# Black_PSI_Controller.net
KiCad netlist of a schematic drawn in EAGLE
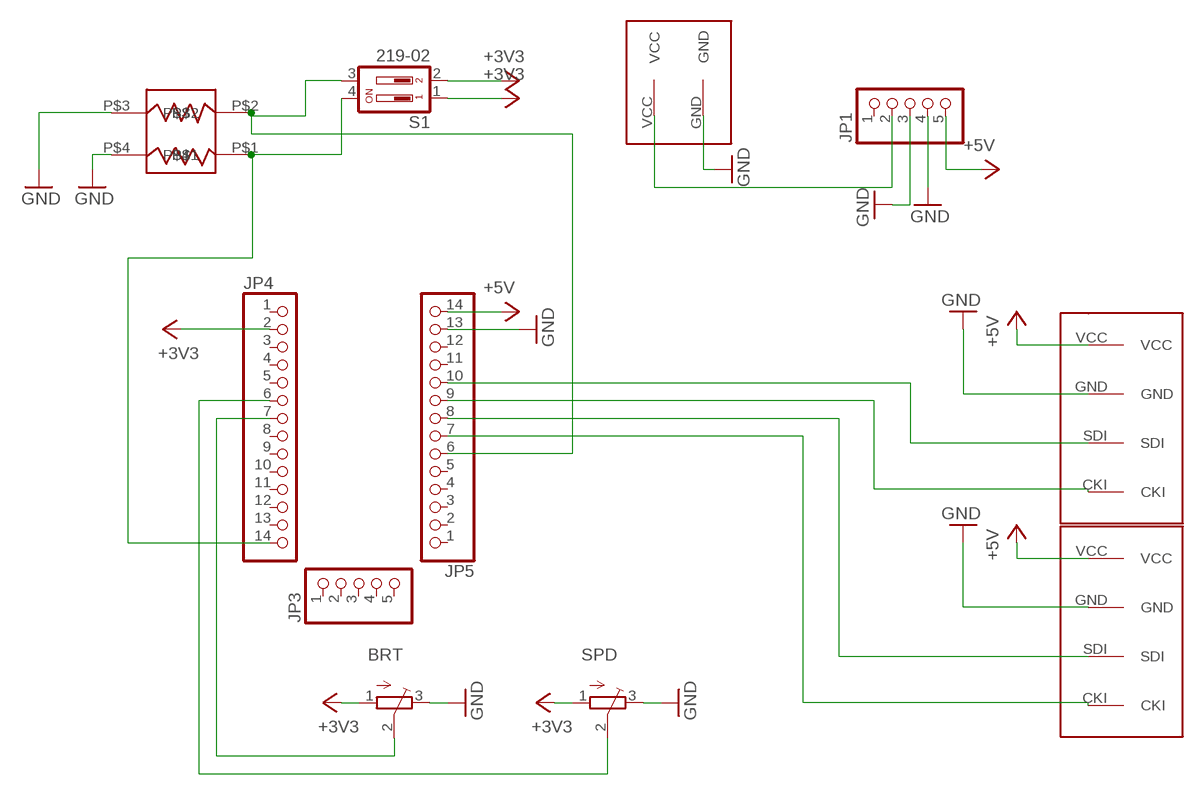
[diagram p0: schematic, sheet 1]

(export (version "E")
  (design (tool "Eeschema 10.0.6"))
  (components
    (comp (ref "BRT")
      (value "TRIMPOTTC33X")
      (footprint "eagle-import:TC33X")
      (libsource (lib "eagle-import") (part "TRIMPOTTC33X"))
    )
    (comp (ref "JP1")
      (value "PINHD-1X5")
      (footprint "eagle-import:1X05")
      (libsource (lib "eagle-import") (part "PINHD-1X5"))
    )
    (comp (ref "JP3")
      (value "PINHD-1X5")
      (footprint "eagle-import:1X05")
      (libsource (lib "eagle-import") (part "PINHD-1X5"))
    )
    (comp (ref "JP4")
      (value "PINHD-1X14")
      (footprint "eagle-import:1X14")
      (libsource (lib "eagle-import") (part "PINHD-1X14"))
    )
    (comp (ref "JP5")
      (value "PINHD-1X14")
      (footprint "eagle-import:1X14")
      (libsource (lib "eagle-import") (part "PINHD-1X14"))
    )
    (comp (ref "S1")
      (value "219-02")
      (footprint "eagle-import:CTS-219-02")
      (libsource (lib "eagle-import") (part "219-02"))
    )
    (comp (ref "SPD")
      (value "TRIMPOTTC33X")
      (footprint "eagle-import:TC33X")
      (libsource (lib "eagle-import") (part "TRIMPOTTC33X"))
    )
    (comp (ref "U$1")
      (value "0393570002WIRE-TO-BOARD")
      (footprint "eagle-import:0393570002WIRE-TO-BOARD")
      (libsource (lib "eagle-import") (part "0393570002WIRE-TO-BOARD"))
    )
    (comp (ref "U$2")
      (value "0393570004WIRE-TO-BOARD")
      (footprint "eagle-import:0393570004WIRE-TO-BOARD")
      (libsource (lib "eagle-import") (part "0393570004WIRE-TO-BOARD"))
    )
    (comp (ref "U$3")
      (value "0393570004WIRE-TO-BOARD")
      (footprint "eagle-import:0393570004WIRE-TO-BOARD")
      (libsource (lib "eagle-import") (part "0393570004WIRE-TO-BOARD"))
    )
    (comp (ref "U$4")
      (value "ACASN1002S1002P1AT")
      (footprint "eagle-import:ACASN1002S1002P1AT")
      (libsource (lib "eagle-import") (part "ACASN1002S1002P1AT"))
    )
  )
  (nets
    (net (code "1") (name "+3V3") (class "Default")
      (node (ref "BRT") (pin "1") (pinfunction "A_1") (pintype "passive"))
      (node (ref "JP4") (pin "2") (pinfunction "2_2") (pintype "passive"))
      (node (ref "S1") (pin "1") (pinfunction "1_1") (pintype "passive"))
      (node (ref "S1") (pin "2") (pinfunction "2_2") (pintype "passive"))
      (node (ref "SPD") (pin "1") (pinfunction "A_1") (pintype "passive"))
    )
    (net (code "2") (name "+5V") (class "Default")
      (node (ref "JP1") (pin "5") (pinfunction "5_5") (pintype "passive"))
      (node (ref "JP5") (pin "14") (pinfunction "14_14") (pintype "passive"))
      (node (ref "U$2") (pin "VCC") (pinfunction "VCC_VCC") (pintype "bidirectional"))
      (node (ref "U$3") (pin "VCC") (pinfunction "VCC_VCC") (pintype "bidirectional"))
    )
    (net (code "3") (name "GND") (class "Default")
      (node (ref "BRT") (pin "3") (pinfunction "E_3") (pintype "passive"))
      (node (ref "JP1") (pin "3") (pinfunction "3_3") (pintype "passive"))
      (node (ref "JP1") (pin "4") (pinfunction "4_4") (pintype "passive"))
      (node (ref "JP5") (pin "13") (pinfunction "13_13") (pintype "passive"))
      (node (ref "SPD") (pin "3") (pinfunction "E_3") (pintype "passive"))
      (node (ref "U$1") (pin "GND") (pinfunction "GND_GND") (pintype "bidirectional"))
      (node (ref "U$2") (pin "GND") (pinfunction "GND_GND") (pintype "bidirectional"))
      (node (ref "U$3") (pin "GND") (pinfunction "GND_GND") (pintype "bidirectional"))
      (node (ref "U$4") (pin "P$3") (pinfunction "P$3_P$3") (pintype "bidirectional"))
      (node (ref "U$4") (pin "P$4") (pinfunction "P$4_P$4") (pintype "bidirectional"))
    )
    (net (code "4") (name "Net-(BRT-S)") (class "Default")
      (node (ref "BRT") (pin "2") (pinfunction "S_2") (pintype "passive"))
      (node (ref "JP4") (pin "7") (pinfunction "7_7") (pintype "passive"))
    )
    (net (code "5") (name "Net-(JP1-Pad2)") (class "Default")
      (node (ref "JP1") (pin "2") (pinfunction "2_2") (pintype "passive"))
      (node (ref "U$1") (pin "VCC") (pinfunction "VCC_VCC") (pintype "bidirectional"))
    )
    (net (code "6") (name "Net-(JP4-Pad14)") (class "Default")
      (node (ref "JP4") (pin "14") (pinfunction "14_14") (pintype "passive"))
      (node (ref "S1") (pin "4") (pinfunction "4_4") (pintype "passive"))
      (node (ref "U$4") (pin "P$1") (pinfunction "P$1_P$1") (pintype "bidirectional"))
    )
    (net (code "7") (name "Net-(JP5-Pad6)") (class "Default")
      (node (ref "JP5") (pin "6") (pinfunction "6_6") (pintype "passive"))
      (node (ref "S1") (pin "3") (pinfunction "3_3") (pintype "passive"))
      (node (ref "U$4") (pin "P$2") (pinfunction "P$2_P$2") (pintype "bidirectional"))
    )
    (net (code "8") (name "Net-(JP5-Pad7)") (class "Default")
      (node (ref "JP5") (pin "7") (pinfunction "7_7") (pintype "passive"))
      (node (ref "U$3") (pin "CKI") (pinfunction "CKI_CKI") (pintype "bidirectional"))
    )
    (net (code "9") (name "Net-(JP5-Pad8)") (class "Default")
      (node (ref "JP5") (pin "8") (pinfunction "8_8") (pintype "passive"))
      (node (ref "U$3") (pin "SDI") (pinfunction "SDI_SDI") (pintype "bidirectional"))
    )
    (net (code "10") (name "Net-(JP5-Pad9)") (class "Default")
      (node (ref "JP5") (pin "9") (pinfunction "9_9") (pintype "passive"))
      (node (ref "U$2") (pin "CKI") (pinfunction "CKI_CKI") (pintype "bidirectional"))
    )
    (net (code "11") (name "Net-(JP5-Pad10)") (class "Default")
      (node (ref "JP5") (pin "10") (pinfunction "10_10") (pintype "passive"))
      (node (ref "U$2") (pin "SDI") (pinfunction "SDI_SDI") (pintype "bidirectional"))
    )
    (net (code "12") (name "Net-(SPD-S)") (class "Default")
      (node (ref "JP4") (pin "6") (pinfunction "6_6") (pintype "passive"))
      (node (ref "SPD") (pin "2") (pinfunction "S_2") (pintype "passive"))
    )
    (net (code "13") (name "unconnected-(JP1-Pad1)") (class "Default")
      (node (ref "JP1") (pin "1") (pinfunction "1_1") (pintype "passive"))
    )
    (net (code "14") (name "unconnected-(JP3-Pad1)") (class "Default")
      (node (ref "JP3") (pin "1") (pinfunction "1_1") (pintype "passive"))
    )
    (net (code "15") (name "unconnected-(JP3-Pad2)") (class "Default")
      (node (ref "JP3") (pin "2") (pinfunction "2_2") (pintype "passive"))
    )
    (net (code "16") (name "unconnected-(JP3-Pad3)") (class "Default")
      (node (ref "JP3") (pin "3") (pinfunction "3_3") (pintype "passive"))
    )
    (net (code "17") (name "unconnected-(JP3-Pad4)") (class "Default")
      (node (ref "JP3") (pin "4") (pinfunction "4_4") (pintype "passive"))
    )
    (net (code "18") (name "unconnected-(JP3-Pad5)") (class "Default")
      (node (ref "JP3") (pin "5") (pinfunction "5_5") (pintype "passive"))
    )
    (net (code "19") (name "unconnected-(JP4-Pad1)") (class "Default")
      (node (ref "JP4") (pin "1") (pinfunction "1_1") (pintype "passive"))
    )
    (net (code "20") (name "unconnected-(JP4-Pad3)") (class "Default")
      (node (ref "JP4") (pin "3") (pinfunction "3_3") (pintype "passive"))
    )
    (net (code "21") (name "unconnected-(JP4-Pad4)") (class "Default")
      (node (ref "JP4") (pin "4") (pinfunction "4_4") (pintype "passive"))
    )
    (net (code "22") (name "unconnected-(JP4-Pad5)") (class "Default")
      (node (ref "JP4") (pin "5") (pinfunction "5_5") (pintype "passive"))
    )
    (net (code "23") (name "unconnected-(JP4-Pad8)") (class "Default")
      (node (ref "JP4") (pin "8") (pinfunction "8_8") (pintype "passive"))
    )
    (net (code "24") (name "unconnected-(JP4-Pad9)") (class "Default")
      (node (ref "JP4") (pin "9") (pinfunction "9_9") (pintype "passive"))
    )
    (net (code "25") (name "unconnected-(JP4-Pad10)") (class "Default")
      (node (ref "JP4") (pin "10") (pinfunction "10_10") (pintype "passive"))
    )
    (net (code "26") (name "unconnected-(JP4-Pad11)") (class "Default")
      (node (ref "JP4") (pin "11") (pinfunction "11_11") (pintype "passive"))
    )
    (net (code "27") (name "unconnected-(JP4-Pad12)") (class "Default")
      (node (ref "JP4") (pin "12") (pinfunction "12_12") (pintype "passive"))
    )
    (net (code "28") (name "unconnected-(JP4-Pad13)") (class "Default")
      (node (ref "JP4") (pin "13") (pinfunction "13_13") (pintype "passive"))
    )
    (net (code "29") (name "unconnected-(JP5-Pad1)") (class "Default")
      (node (ref "JP5") (pin "1") (pinfunction "1_1") (pintype "passive"))
    )
    (net (code "30") (name "unconnected-(JP5-Pad2)") (class "Default")
      (node (ref "JP5") (pin "2") (pinfunction "2_2") (pintype "passive"))
    )
    (net (code "31") (name "unconnected-(JP5-Pad3)") (class "Default")
      (node (ref "JP5") (pin "3") (pinfunction "3_3") (pintype "passive"))
    )
    (net (code "32") (name "unconnected-(JP5-Pad4)") (class "Default")
      (node (ref "JP5") (pin "4") (pinfunction "4_4") (pintype "passive"))
    )
    (net (code "33") (name "unconnected-(JP5-Pad5)") (class "Default")
      (node (ref "JP5") (pin "5") (pinfunction "5_5") (pintype "passive"))
    )
    (net (code "34") (name "unconnected-(JP5-Pad11)") (class "Default")
      (node (ref "JP5") (pin "11") (pinfunction "11_11") (pintype "passive"))
    )
    (net (code "35") (name "unconnected-(JP5-Pad12)") (class "Default")
      (node (ref "JP5") (pin "12") (pinfunction "12_12") (pintype "passive"))
    )
  )
)
